# USBC_PD_CC_TUSB320.net
KiCad netlist of a schematic drawn in Altium Designer
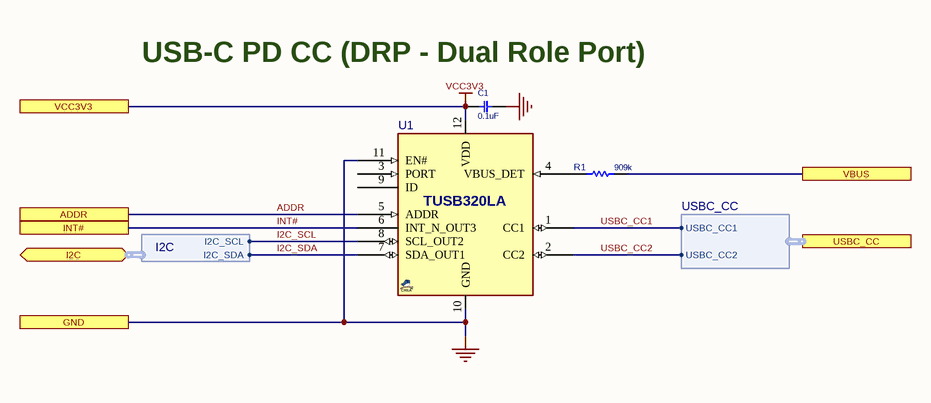
[diagram p0: USBC_PD_CC_TUSB320.SchDoc]

(export (version "E")
  (design (tool "Eeschema 10.0.6"))
  (components
    (comp (ref "C1")
      (value "0.1uF")
      (footprint "C0201")
      (description "CAP, MLCC")
      (fields (field (name "MANF_P#") "CL03A104KP3NNWC") (field (name "MANF") "Samsung"))
      (libsource (lib "passive_smd") (part "CAP_SMD_MLCC"))
    )
    (comp (ref "R1")
      (value "909k")
      (footprint "R0402")
      (description "RESISTOR, SMD")
      (libsource (lib "passive_res_smd") (part "RES_SMD"))
    )
    (comp (ref "U1")
      (value "TUSB320LA")
      (footprint "QFN40_12_1616")
      (description "USB-C PD controller")
      (fields (field (name "MANF") "Texas Instruments") (field (name "MANF_1") "MANF"))
      (libsource (lib "usbc_pd_cc_control") (part "TUSB320LA_X2QFN12"))
    )
  )
  (nets
    (net (code "3") (name "/ADDR") (class "Default")
      (node (ref "U1") (pin "5") (pinfunction "ADDR_5") (pintype "input"))
    )
    (net (code "4") (name "/I2C_SCL") (class "Default")
      (node (ref "U1") (pin "8") (pinfunction "SCL_OUT2_8") (pintype "bidirectional"))
    )
    (net (code "5") (name "/I2C_SDA") (class "Default")
      (node (ref "U1") (pin "7") (pinfunction "SDA_OUT1_7") (pintype "bidirectional"))
    )
    (net (code "6") (name "/INT#") (class "Default")
      (node (ref "U1") (pin "6") (pinfunction "INT_N_OUT3_6") (pintype "open_collector"))
    )
    (net (code "7") (name "/USBC_CC1") (class "Default")
      (node (ref "U1") (pin "1") (pinfunction "CC1_1") (pintype "bidirectional"))
    )
    (net (code "8") (name "/USBC_CC2") (class "Default")
      (node (ref "U1") (pin "2") (pinfunction "CC2_2") (pintype "bidirectional"))
    )
    (net (code "9") (name "/VBUS") (class "Default")
      (node (ref "R1") (pin "2") (pinfunction "2_2") (pintype "passive"))
    )
    (net (code "12") (name "GND") (class "Default")
      (node (ref "C1") (pin "2") (pinfunction "2_2") (pintype "passive"))
      (node (ref "U1") (pin "10") (pinfunction "GND_10") (pintype "power_in"))
      (node (ref "U1") (pin "11") (pinfunction "EN#_11") (pintype "input"))
    )
    (net (code "13") (name "Net-(U1-VBUS_DET)") (class "Default")
      (node (ref "R1") (pin "1") (pinfunction "1_1") (pintype "passive"))
      (node (ref "U1") (pin "4") (pinfunction "VBUS_DET_4") (pintype "input"))
    )
    (net (code "14") (name "VCC3V3") (class "Default")
      (node (ref "C1") (pin "1") (pinfunction "1_1") (pintype "passive"))
      (node (ref "U1") (pin "12") (pinfunction "VDD_12") (pintype "power_in"))
    )
    (net (code "15") (name "unconnected-(U1-ID-Pad9)") (class "Default")
      (node (ref "U1") (pin "9") (pinfunction "ID_9") (pintype "open_collector"))
    )
    (net (code "16") (name "unconnected-(U1-PORT-Pad3)") (class "Default")
      (node (ref "U1") (pin "3") (pinfunction "PORT_3") (pintype "input"))
    )
  )
)
